# Fdbk_2.net
KiCad netlist of a schematic drawn in Altium Designer
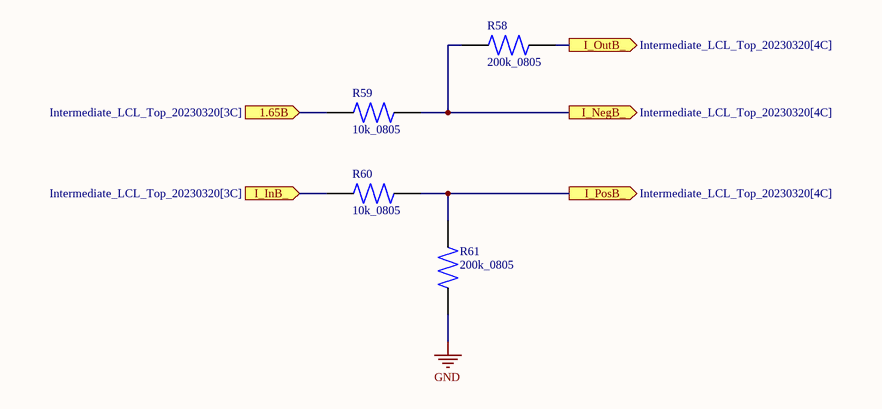
[diagram p0: Fdbk_2.SchDoc]

(export (version "E")
  (design (tool "Eeschema 10.0.6"))
  (components
    (comp (ref "R58")
      (value "200k_0805")
      (footprint "FYP_Components:0805 Resistor")
      (description "SMD Chip Resistor, 200 kohm, ± 1%, 125 mW, 0805 [2012 Metric], Thick Film, General Purpose")
      (fields (field (name "MF") "Bourns") (field (name "MP") "CRE2512-FZ-R007E-3"))
      (libsource (lib "FYP_Components") (part "CRCW0805200KFKEA"))
    )
    (comp (ref "R59")
      (value "10k_0805")
      (footprint "FYP_Components:0805 Resistor")
      (description "SMD Chip Resistor, 10 kohm, ± 1%, 125 mW, 0805 [2012 Metric], Thick Film, General Purpose")
      (fields (field (name "MF") "Bourns") (field (name "MP") "CRE2512-FZ-R007E-3"))
      (libsource (lib "FYP_Components") (part "CRCW080510K0FKEA"))
    )
    (comp (ref "R60")
      (value "10k_0805")
      (footprint "FYP_Components:0805 Resistor")
      (description "SMD Chip Resistor, 10 kohm, ± 1%, 125 mW, 0805 [2012 Metric], Thick Film, General Purpose")
      (fields (field (name "MF") "Bourns") (field (name "MP") "CRE2512-FZ-R007E-3"))
      (libsource (lib "FYP_Components") (part "CRCW080510K0FKEA"))
    )
    (comp (ref "R61")
      (value "200k_0805")
      (footprint "FYP_Components:0805 Resistor")
      (description "SMD Chip Resistor, 200 kohm, ± 1%, 125 mW, 0805 [2012 Metric], Thick Film, General Purpose")
      (fields (field (name "MF") "Bourns") (field (name "MP") "CRE2512-FZ-R007E-3"))
      (libsource (lib "FYP_Components") (part "CRCW0805200KFKEA"))
    )
  )
  (nets
    (net (code "1") (name "/1.65B") (class "Default")
      (node (ref "R59") (pin "1") (pinfunction "1_1") (pintype "passive"))
    )
    (net (code "2") (name "/I_InB_") (class "Default")
      (node (ref "R60") (pin "1") (pinfunction "1_1") (pintype "passive"))
    )
    (net (code "3") (name "/I_NegB_") (class "Default")
      (node (ref "R58") (pin "1") (pinfunction "1_1") (pintype "passive"))
      (node (ref "R59") (pin "2") (pinfunction "2_2") (pintype "passive"))
    )
    (net (code "4") (name "/I_OutB_") (class "Default")
      (node (ref "R58") (pin "2") (pinfunction "2_2") (pintype "passive"))
    )
    (net (code "5") (name "/I_PosB_") (class "Default")
      (node (ref "R60") (pin "2") (pinfunction "2_2") (pintype "passive"))
      (node (ref "R61") (pin "2") (pinfunction "2_2") (pintype "passive"))
    )
    (net (code "6") (name "GND") (class "Default")
      (node (ref "R61") (pin "1") (pinfunction "1_1") (pintype "passive"))
    )
  )
)
